# Ninjahub.net
KiCad netlist of a schematic drawn in EasyEDA Pro
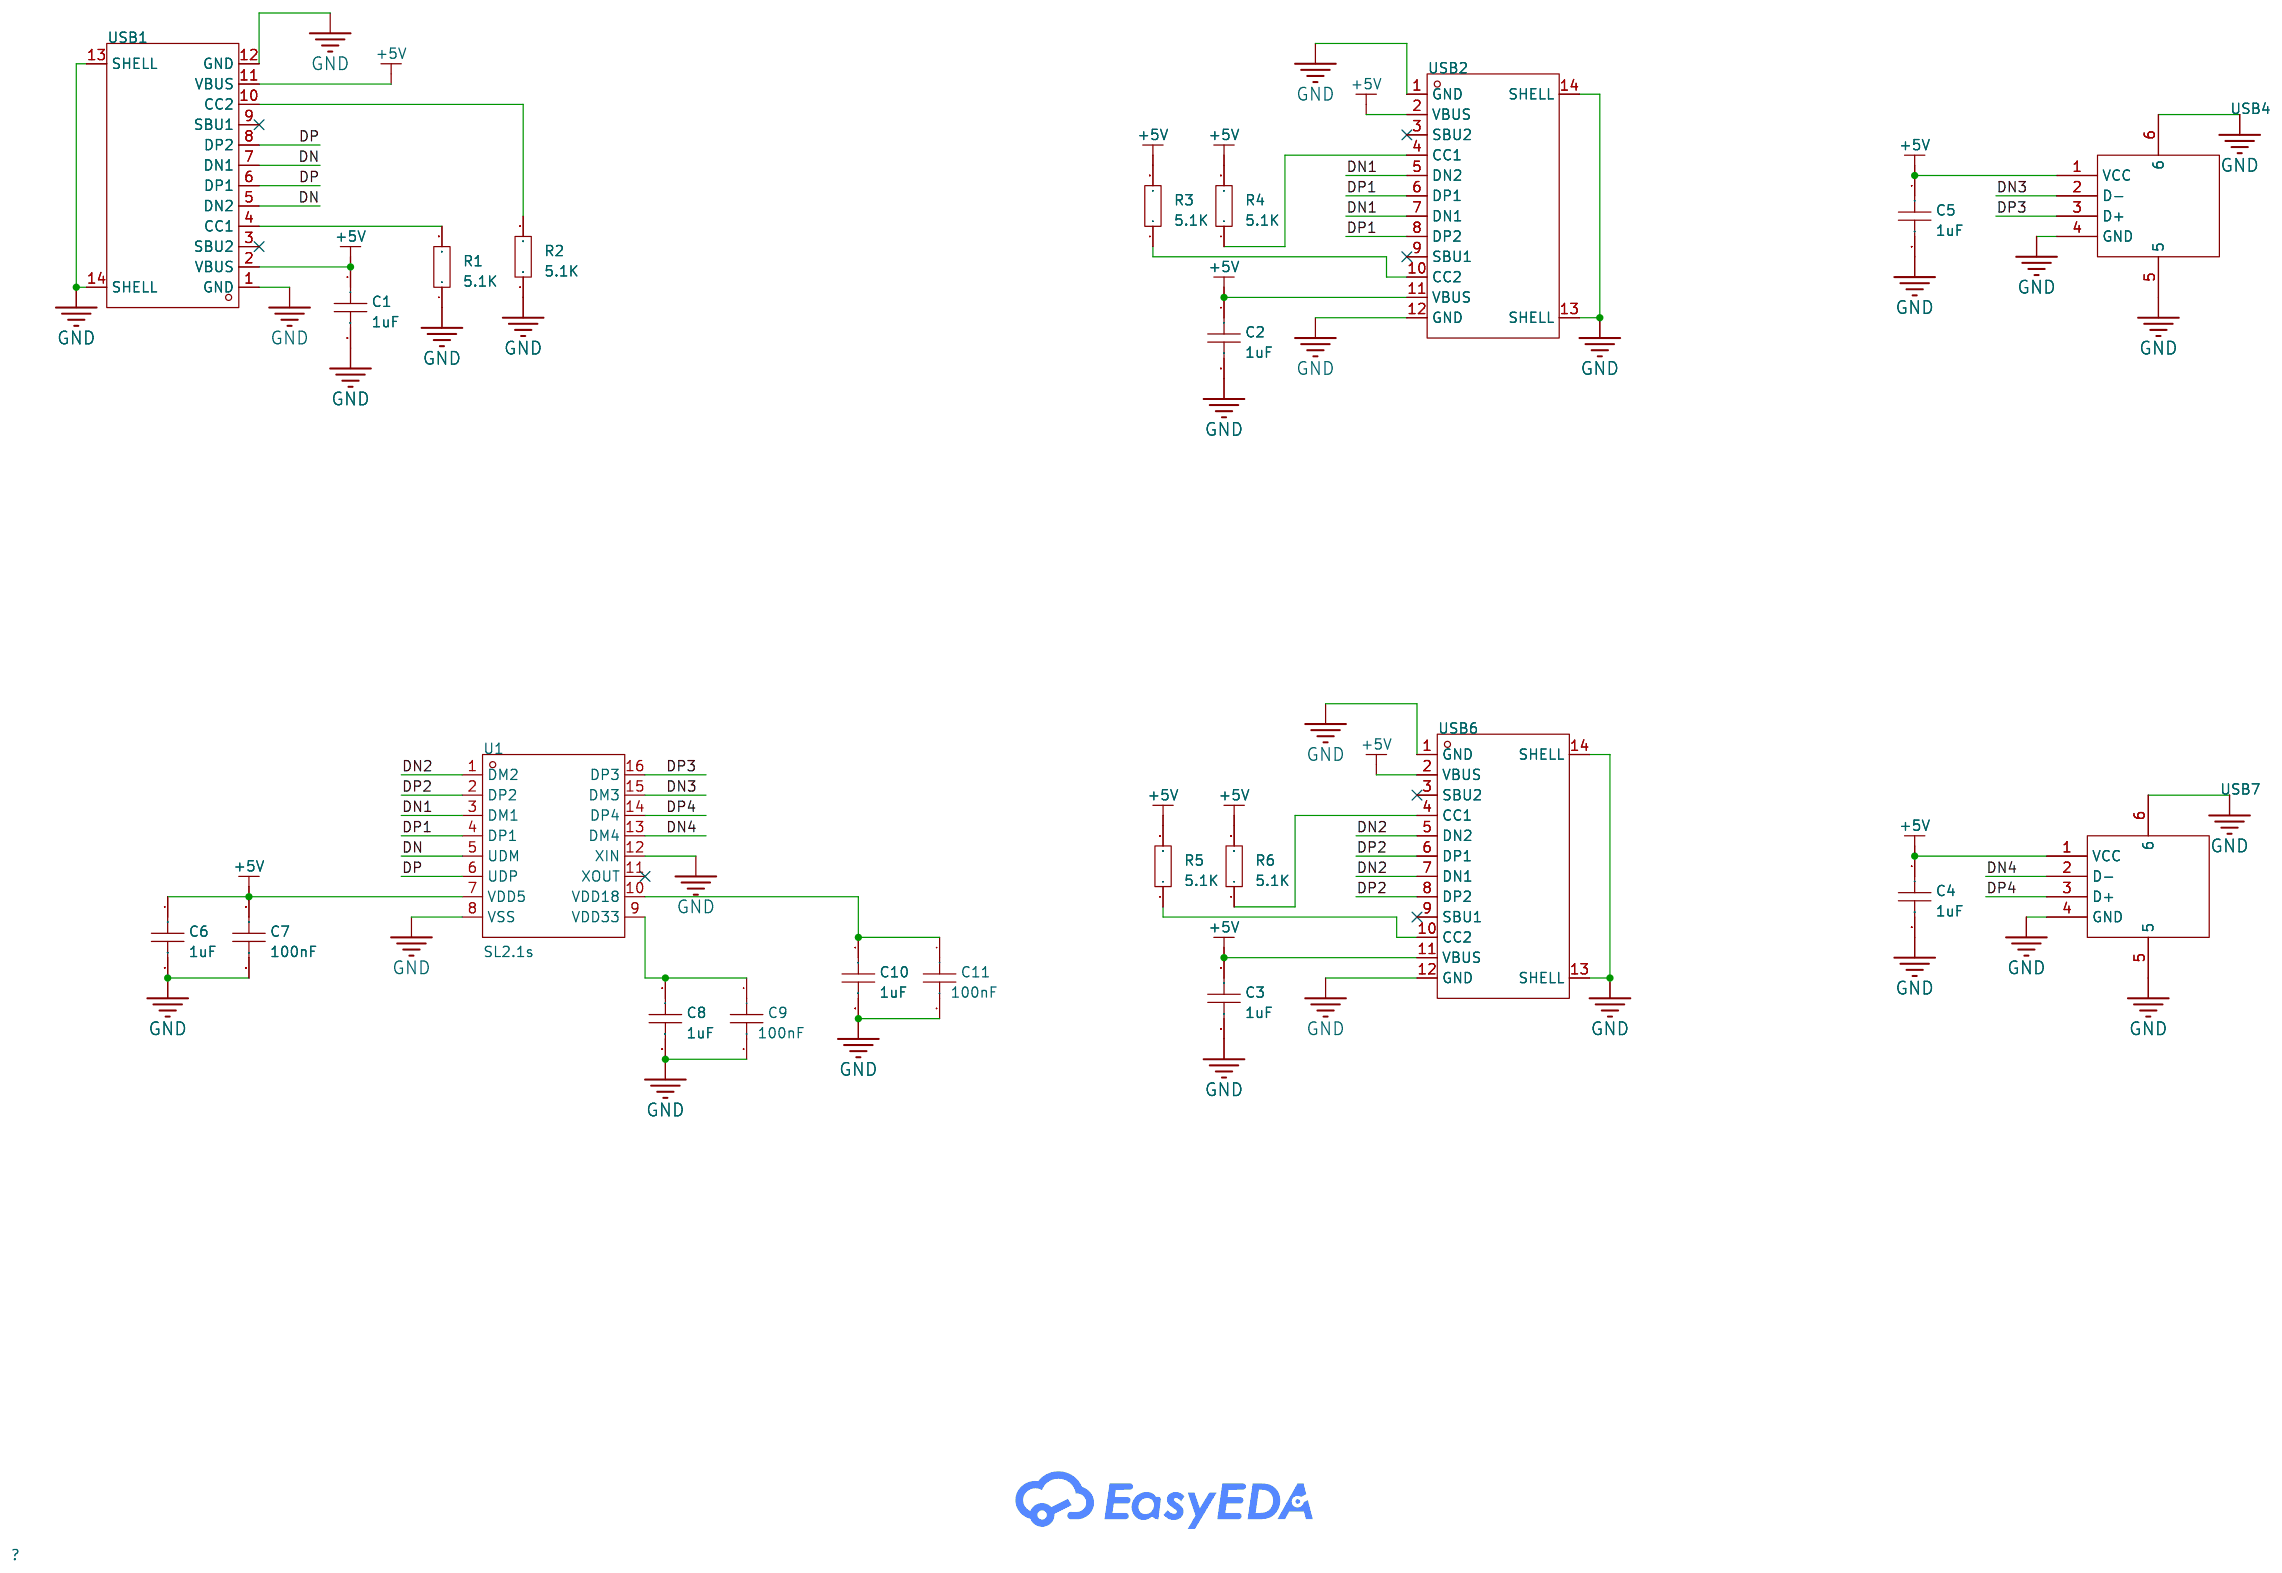
[diagram p0: schematic sheet]

(export (version "E")
  (design (tool "Eeschema 10.0.6"))
  (components
    (comp (ref "C1") (value "1uF") (footprint "easyedapro:C0603") (libsource (lib "easyedapro") (part "CAP")))
    (comp (ref "C2") (value "1uF") (footprint "easyedapro:C0603") (libsource (lib "easyedapro") (part "CAP")))
    (comp (ref "C3") (value "1uF") (footprint "easyedapro:C0603") (libsource (lib "easyedapro") (part "CAP")))
    (comp (ref "C4") (value "1uF") (footprint "easyedapro:C0603") (libsource (lib "easyedapro") (part "CAP")))
    (comp (ref "C5") (value "1uF") (footprint "easyedapro:C0603") (libsource (lib "easyedapro") (part "CAP")))
    (comp (ref "C6") (value "1uF") (footprint "easyedapro:C0603") (libsource (lib "easyedapro") (part "CAP")))
    (comp (ref "C7")
      (value "100nF")
      (footprint "easyedapro:C0603")
      (libsource (lib "easyedapro") (part "CAP"))
    )
    (comp (ref "C8") (value "1uF") (footprint "easyedapro:C0603") (libsource (lib "easyedapro") (part "CAP")))
    (comp (ref "C9")
      (value "100nF")
      (footprint "easyedapro:C0603")
      (libsource (lib "easyedapro") (part "CAP"))
    )
    (comp (ref "C10")
      (value "1uF")
      (footprint "easyedapro:C0603")
      (libsource (lib "easyedapro") (part "CAP"))
    )
    (comp (ref "C11")
      (value "100nF")
      (footprint "easyedapro:C0603")
      (libsource (lib "easyedapro") (part "CAP"))
    )
    (comp (ref "R1")
      (value "5.1K")
      (footprint "easyedapro:R0603")
      (libsource (lib "easyedapro") (part "Res"))
    )
    (comp (ref "R2")
      (value "5.1K")
      (footprint "easyedapro:R0603")
      (libsource (lib "easyedapro") (part "Res"))
    )
    (comp (ref "R3")
      (value "5.1K")
      (footprint "easyedapro:R0603")
      (libsource (lib "easyedapro") (part "Res"))
    )
    (comp (ref "R4")
      (value "5.1K")
      (footprint "easyedapro:R0603")
      (libsource (lib "easyedapro") (part "Res"))
    )
    (comp (ref "R5")
      (value "5.1K")
      (footprint "easyedapro:R0603")
      (libsource (lib "easyedapro") (part "Res"))
    )
    (comp (ref "R6")
      (value "5.1K")
      (footprint "easyedapro:R0603")
      (libsource (lib "easyedapro") (part "Res"))
    )
    (comp (ref "U1")
      (value "SL2.1s")
      (footprint "easyedapro:SSOP-16_L4.6-W2.6-P0.53-LS4.0-BL")
      (fields (field (name "Manufacturer") "CoreChips(和芯润德)"))
      (libsource (lib "easyedapro") (part "SL2.1S"))
    )
    (comp (ref "USB1")
      (value "TYPE-C 16PIN 2MD(073)")
      (footprint "easyedapro:USB-C-SMD_TYPE-C-6PIN-2MD-073")
      (fields (field (name "Manufacturer") "SHOU HAN(首韩)"))
      (libsource (lib "easyedapro") (part "TYPE-C 16PIN 2MD(073)"))
    )
    (comp (ref "USB2")
      (value "TYPE-C 16PIN 2MD(073)")
      (footprint "easyedapro:USB-C-SMD_TYPE-C-6PIN-2MD-073")
      (fields (field (name "Manufacturer") "SHOU HAN(首韩)"))
      (libsource (lib "easyedapro") (part "TYPE-C 16PIN 2MD(073)"))
    )
    (comp (ref "USB4")
      (value "10.0 QHHTZB6.3")
      (footprint "easyedapro:USB-A-TH_10.0QHHTZB6.3")
      (fields (field (name "Manufacturer") "SHOU HAN(首韩)"))
      (libsource (lib "easyedapro") (part "10.0 QHHTZB6.3"))
    )
    (comp (ref "USB6")
      (value "TYPE-C 16PIN 2MD(073)")
      (footprint "easyedapro:USB-C-SMD_TYPE-C-6PIN-2MD-073")
      (fields (field (name "Manufacturer") "SHOU HAN(首韩)"))
      (libsource (lib "easyedapro") (part "TYPE-C 16PIN 2MD(073)"))
    )
    (comp (ref "USB7")
      (value "10.0 QHHTZB6.3")
      (footprint "easyedapro:USB-A-TH_10.0QHHTZB6.3")
      (fields (field (name "Manufacturer") "SHOU HAN(首韩)"))
      (libsource (lib "easyedapro") (part "10.0 QHHTZB6.3"))
    )
  )
  (nets
    (net (code "1") (name "+5V") (class "Default")
      (node (ref "C1") (pin "1") (pinfunction "1_1") (pintype "input"))
      (node (ref "C2") (pin "1") (pinfunction "1_1") (pintype "input"))
      (node (ref "C3") (pin "1") (pinfunction "1_1") (pintype "input"))
      (node (ref "C4") (pin "1") (pinfunction "1_1") (pintype "input"))
      (node (ref "C5") (pin "1") (pinfunction "1_1") (pintype "input"))
      (node (ref "C6") (pin "1") (pinfunction "1_1") (pintype "input"))
      (node (ref "C7") (pin "1") (pinfunction "1_1") (pintype "input"))
      (node (ref "R3") (pin "2") (pinfunction "2_2") (pintype "input"))
      (node (ref "R4") (pin "2") (pinfunction "2_2") (pintype "input"))
      (node (ref "R5") (pin "2") (pinfunction "2_2") (pintype "input"))
      (node (ref "R6") (pin "2") (pinfunction "2_2") (pintype "input"))
      (node (ref "U1") (pin "7") (pinfunction "VDD5_7") (pintype "unspecified"))
      (node (ref "USB1") (pin "11") (pinfunction "VBUS_11") (pintype "unspecified"))
      (node (ref "USB1") (pin "2") (pinfunction "VBUS_2") (pintype "unspecified"))
      (node (ref "USB2") (pin "11") (pinfunction "VBUS_11") (pintype "unspecified"))
      (node (ref "USB2") (pin "2") (pinfunction "VBUS_2") (pintype "unspecified"))
      (node (ref "USB4") (pin "1") (pinfunction "VCC_1") (pintype "unspecified"))
      (node (ref "USB6") (pin "11") (pinfunction "VBUS_11") (pintype "unspecified"))
      (node (ref "USB6") (pin "2") (pinfunction "VBUS_2") (pintype "unspecified"))
      (node (ref "USB7") (pin "1") (pinfunction "VCC_1") (pintype "unspecified"))
    )
    (net (code "2") (name "/DN") (class "Default")
      (node (ref "U1") (pin "5") (pinfunction "UDM_5") (pintype "unspecified"))
      (node (ref "USB1") (pin "5") (pinfunction "DN2_5") (pintype "unspecified"))
      (node (ref "USB1") (pin "7") (pinfunction "DN1_7") (pintype "unspecified"))
    )
    (net (code "3") (name "/DN1") (class "Default")
      (node (ref "U1") (pin "3") (pinfunction "DM1_3") (pintype "unspecified"))
      (node (ref "USB2") (pin "5") (pinfunction "DN2_5") (pintype "unspecified"))
      (node (ref "USB2") (pin "7") (pinfunction "DN1_7") (pintype "unspecified"))
    )
    (net (code "4") (name "/DN2") (class "Default")
      (node (ref "U1") (pin "1") (pinfunction "DM2_1") (pintype "unspecified"))
      (node (ref "USB6") (pin "5") (pinfunction "DN2_5") (pintype "unspecified"))
      (node (ref "USB6") (pin "7") (pinfunction "DN1_7") (pintype "unspecified"))
    )
    (net (code "5") (name "/DN3") (class "Default")
      (node (ref "U1") (pin "15") (pinfunction "DM3_15") (pintype "unspecified"))
      (node (ref "USB4") (pin "2") (pinfunction "D-_2") (pintype "unspecified"))
    )
    (net (code "6") (name "/DN4") (class "Default")
      (node (ref "U1") (pin "13") (pinfunction "DM4_13") (pintype "unspecified"))
      (node (ref "USB7") (pin "2") (pinfunction "D-_2") (pintype "unspecified"))
    )
    (net (code "7") (name "/DP") (class "Default")
      (node (ref "U1") (pin "6") (pinfunction "UDP_6") (pintype "unspecified"))
      (node (ref "USB1") (pin "6") (pinfunction "DP1_6") (pintype "unspecified"))
      (node (ref "USB1") (pin "8") (pinfunction "DP2_8") (pintype "unspecified"))
    )
    (net (code "8") (name "/DP1") (class "Default")
      (node (ref "U1") (pin "4") (pinfunction "DP1_4") (pintype "unspecified"))
      (node (ref "USB2") (pin "6") (pinfunction "DP1_6") (pintype "unspecified"))
      (node (ref "USB2") (pin "8") (pinfunction "DP2_8") (pintype "unspecified"))
    )
    (net (code "9") (name "/DP2") (class "Default")
      (node (ref "U1") (pin "2") (pinfunction "DP2_2") (pintype "unspecified"))
      (node (ref "USB6") (pin "6") (pinfunction "DP1_6") (pintype "unspecified"))
      (node (ref "USB6") (pin "8") (pinfunction "DP2_8") (pintype "unspecified"))
    )
    (net (code "10") (name "/DP3") (class "Default")
      (node (ref "U1") (pin "16") (pinfunction "DP3_16") (pintype "unspecified"))
      (node (ref "USB4") (pin "3") (pinfunction "D+_3") (pintype "unspecified"))
    )
    (net (code "11") (name "/DP4") (class "Default")
      (node (ref "U1") (pin "14") (pinfunction "DP4_14") (pintype "unspecified"))
      (node (ref "USB7") (pin "3") (pinfunction "D+_3") (pintype "unspecified"))
    )
    (net (code "12") (name "GND") (class "Default")
      (node (ref "C1") (pin "2") (pinfunction "2_2") (pintype "input"))
      (node (ref "C10") (pin "2") (pinfunction "2_2") (pintype "input"))
      (node (ref "C11") (pin "2") (pinfunction "2_2") (pintype "input"))
      (node (ref "C2") (pin "2") (pinfunction "2_2") (pintype "input"))
      (node (ref "C3") (pin "2") (pinfunction "2_2") (pintype "input"))
      (node (ref "C4") (pin "2") (pinfunction "2_2") (pintype "input"))
      (node (ref "C5") (pin "2") (pinfunction "2_2") (pintype "input"))
      (node (ref "C6") (pin "2") (pinfunction "2_2") (pintype "input"))
      (node (ref "C7") (pin "2") (pinfunction "2_2") (pintype "input"))
      (node (ref "C8") (pin "2") (pinfunction "2_2") (pintype "input"))
      (node (ref "C9") (pin "2") (pinfunction "2_2") (pintype "input"))
      (node (ref "R1") (pin "1") (pinfunction "1_1") (pintype "input"))
      (node (ref "R2") (pin "1") (pinfunction "1_1") (pintype "input"))
      (node (ref "U1") (pin "12") (pinfunction "XIN_12") (pintype "unspecified"))
      (node (ref "U1") (pin "8") (pinfunction "VSS_8") (pintype "unspecified"))
      (node (ref "USB1") (pin "1") (pinfunction "GND_1") (pintype "unspecified"))
      (node (ref "USB1") (pin "12") (pinfunction "GND_12") (pintype "unspecified"))
      (node (ref "USB1") (pin "13") (pinfunction "SHELL_13") (pintype "unspecified"))
      (node (ref "USB1") (pin "14") (pinfunction "SHELL_14") (pintype "unspecified"))
      (node (ref "USB2") (pin "1") (pinfunction "GND_1") (pintype "unspecified"))
      (node (ref "USB2") (pin "12") (pinfunction "GND_12") (pintype "unspecified"))
      (node (ref "USB2") (pin "13") (pinfunction "SHELL_13") (pintype "unspecified"))
      (node (ref "USB2") (pin "14") (pinfunction "SHELL_14") (pintype "unspecified"))
      (node (ref "USB4") (pin "4") (pinfunction "GND_4") (pintype "unspecified"))
      (node (ref "USB4") (pin "5") (pinfunction "5_5") (pintype "unspecified"))
      (node (ref "USB4") (pin "6") (pinfunction "6_6") (pintype "unspecified"))
      (node (ref "USB6") (pin "1") (pinfunction "GND_1") (pintype "unspecified"))
      (node (ref "USB6") (pin "12") (pinfunction "GND_12") (pintype "unspecified"))
      (node (ref "USB6") (pin "13") (pinfunction "SHELL_13") (pintype "unspecified"))
      (node (ref "USB6") (pin "14") (pinfunction "SHELL_14") (pintype "unspecified"))
      (node (ref "USB7") (pin "4") (pinfunction "GND_4") (pintype "unspecified"))
      (node (ref "USB7") (pin "5") (pinfunction "5_5") (pintype "unspecified"))
      (node (ref "USB7") (pin "6") (pinfunction "6_6") (pintype "unspecified"))
    )
    (net (code "13") (name "Net-(U1-VDD18)") (class "Default")
      (node (ref "C10") (pin "1") (pinfunction "1_1") (pintype "input"))
      (node (ref "C11") (pin "1") (pinfunction "1_1") (pintype "input"))
      (node (ref "U1") (pin "10") (pinfunction "VDD18_10") (pintype "unspecified"))
    )
    (net (code "14") (name "Net-(U1-VDD33)") (class "Default")
      (node (ref "C8") (pin "1") (pinfunction "1_1") (pintype "input"))
      (node (ref "C9") (pin "1") (pinfunction "1_1") (pintype "input"))
      (node (ref "U1") (pin "9") (pinfunction "VDD33_9") (pintype "unspecified"))
    )
    (net (code "15") (name "Net-(USB1-CC1)") (class "Default")
      (node (ref "R1") (pin "2") (pinfunction "2_2") (pintype "input"))
      (node (ref "USB1") (pin "4") (pinfunction "CC1_4") (pintype "unspecified"))
    )
    (net (code "16") (name "Net-(USB1-CC2)") (class "Default")
      (node (ref "R2") (pin "2") (pinfunction "2_2") (pintype "input"))
      (node (ref "USB1") (pin "10") (pinfunction "CC2_10") (pintype "unspecified"))
    )
    (net (code "17") (name "Net-(USB2-CC1)") (class "Default")
      (node (ref "R4") (pin "1") (pinfunction "1_1") (pintype "input"))
      (node (ref "USB2") (pin "4") (pinfunction "CC1_4") (pintype "unspecified"))
    )
    (net (code "18") (name "Net-(USB2-CC2)") (class "Default")
      (node (ref "R3") (pin "1") (pinfunction "1_1") (pintype "input"))
      (node (ref "USB2") (pin "10") (pinfunction "CC2_10") (pintype "unspecified"))
    )
    (net (code "19") (name "Net-(USB6-CC1)") (class "Default")
      (node (ref "R6") (pin "1") (pinfunction "1_1") (pintype "input"))
      (node (ref "USB6") (pin "4") (pinfunction "CC1_4") (pintype "unspecified"))
    )
    (net (code "20") (name "Net-(USB6-CC2)") (class "Default")
      (node (ref "R5") (pin "1") (pinfunction "1_1") (pintype "input"))
      (node (ref "USB6") (pin "10") (pinfunction "CC2_10") (pintype "unspecified"))
    )
    (net (code "21") (name "unconnected-(U1-XOUT-Pad11)") (class "Default")
      (node (ref "U1") (pin "11") (pinfunction "XOUT_11") (pintype "unspecified+no_connect"))
    )
    (net (code "22") (name "unconnected-(USB1-SBU1-Pad9)") (class "Default")
      (node (ref "USB1") (pin "9") (pinfunction "SBU1_9") (pintype "unspecified+no_connect"))
    )
    (net (code "23") (name "unconnected-(USB1-SBU2-Pad3)") (class "Default")
      (node (ref "USB1") (pin "3") (pinfunction "SBU2_3") (pintype "unspecified+no_connect"))
    )
    (net (code "24") (name "unconnected-(USB2-SBU1-Pad9)") (class "Default")
      (node (ref "USB2") (pin "9") (pinfunction "SBU1_9") (pintype "unspecified+no_connect"))
    )
    (net (code "25") (name "unconnected-(USB2-SBU2-Pad3)") (class "Default")
      (node (ref "USB2") (pin "3") (pinfunction "SBU2_3") (pintype "unspecified+no_connect"))
    )
    (net (code "26") (name "unconnected-(USB6-SBU1-Pad9)") (class "Default")
      (node (ref "USB6") (pin "9") (pinfunction "SBU1_9") (pintype "unspecified+no_connect"))
    )
    (net (code "27") (name "unconnected-(USB6-SBU2-Pad3)") (class "Default")
      (node (ref "USB6") (pin "3") (pinfunction "SBU2_3") (pintype "unspecified+no_connect"))
    )
  )
)
